# SAMR21_Xplained_Pro_Crystals.net
KiCad netlist of a schematic drawn in Altium Designer
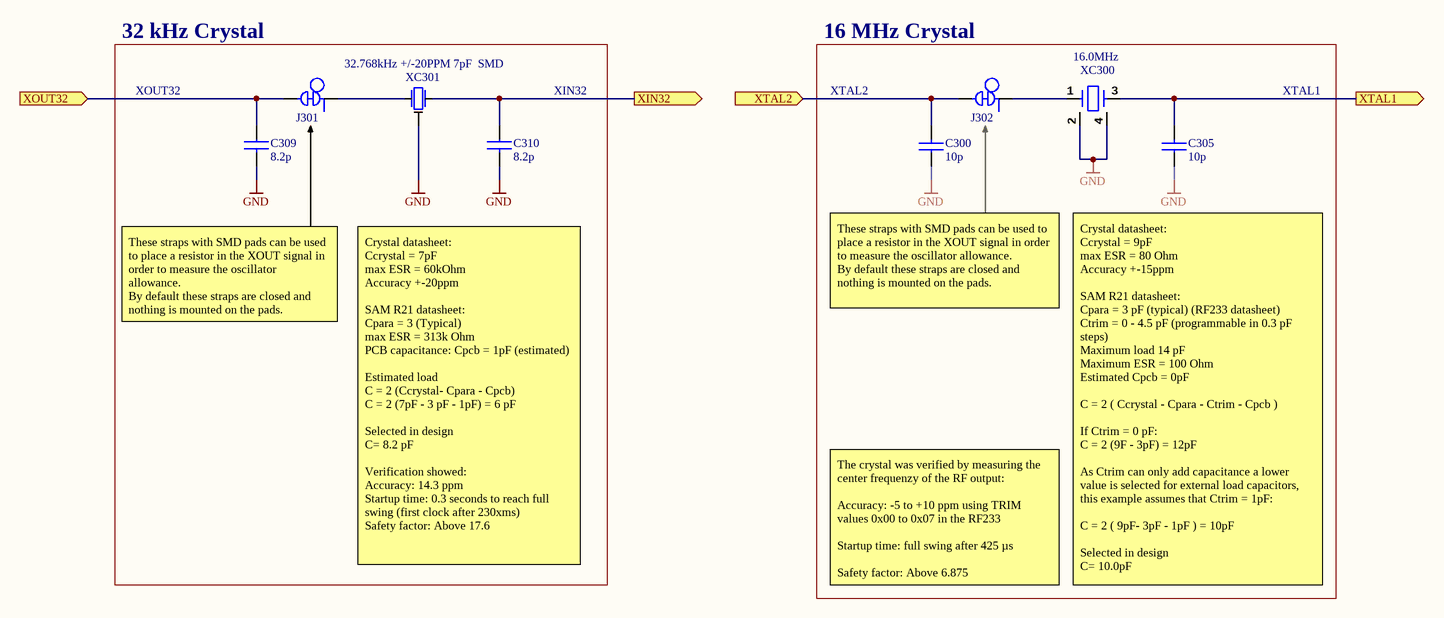
[diagram p0: SAMR21_Xplained_Pro_Crystals.SchDoc]

(export (version "E")
  (design (tool "Eeschema 10.0.6"))
  (components
    (comp (ref "C300")
      (value "10p")
      (footprint "AP1-00001")
      (description "Ceramic capacitor, SMD 0402, NP0, 50V, +/-5%")
      (fields (field (name "TOLERANCE") "50V, +/-5%") (field (name "Comment") "CAP-NONPOL"))
      (libsource (lib "AltiumDbLib") (part "CAP-NONPOL"))
    )
    (comp (ref "C305")
      (value "10p")
      (footprint "AP1-00001")
      (description "Ceramic capacitor, SMD 0402, NP0, 50V, +/-5%")
      (fields (field (name "TOLERANCE") "50V, +/-5%") (field (name "Comment") "CAP-NONPOL"))
      (libsource (lib "AltiumDbLib") (part "CAP-NONPOL"))
    )
    (comp (ref "C309")
      (value "8.2p")
      (footprint "AP1-00001")
      (description "Ceramic capacitor, SMD 0402, NP0, 50V, +/-5%")
      (fields (field (name "TOLERANCE") "50V, +/-5%") (field (name "Comment") "CAP-NONPOL"))
      (libsource (lib "AltiumDbLib") (part "CAP-NONPOL"))
    )
    (comp (ref "C310")
      (value "8.2p")
      (footprint "AP1-00001")
      (description "Ceramic capacitor, SMD 0402, NP0, 50V, +/-5%")
      (fields (field (name "TOLERANCE") "50V, +/-5%") (field (name "Comment") "CAP-NONPOL"))
      (libsource (lib "AltiumDbLib") (part "CAP-NONPOL"))
    )
    (comp (ref "J301")
      (value "SMD-STRAP_CLOSED")
      (footprint "AP8-00595")
      (description "Closed Link 0402")
      (libsource (lib "AltiumDbLib") (part "SMD-STRAP_CLOSED"))
    )
    (comp (ref "J302")
      (value "SMD-STRAP_CLOSED")
      (footprint "AP8-00595")
      (description "Closed Link 0402")
      (libsource (lib "AltiumDbLib") (part "SMD-STRAP_CLOSED"))
    )
    (comp (ref "XC300")
      (value "16.0MHz")
      (footprint "AP7-00061")
      (description "16MHz uXtal, 3.2 x 2.5 mm SMD, CL=9pF, 15PPM, ESR=80ohm(Max.")
      (fields (field (name "TOLERANCE") "15ppm") (field (name "MANUFACTURER") "Epson Toyocom"))
      (libsource (lib "AltiumDbLib") (part "TSX-3225"))
    )
    (comp (ref "XC301")
      (value "32.768kHz +/-20PPM 7pF  SMD")
      (footprint "AP7-00044")
      (description "32k768 crystal, +-20ppm, CL=7pF, max ESR 60kOhm, SMD")
      (fields (field (name "TOLERANCE") "+/- 20 PPM") (field (name "MANUFACTURER") "Micro Crystal"))
      (libsource (lib "AltiumDbLib") (part "CRYSTAL_2P_metal"))
    )
  )
  (nets
    (net (code "1") (name "/XIN32") (class "Default")
      (node (ref "C310") (pin "1") (pinfunction "1_1") (pintype "passive"))
      (node (ref "XC301") (pin "2") (pinfunction "2_2") (pintype "passive"))
    )
    (net (code "2") (name "/XOUT32") (class "Default")
      (node (ref "C309") (pin "1") (pinfunction "1_1") (pintype "passive"))
      (node (ref "J301") (pin "2") (pinfunction "2_2") (pintype "passive"))
    )
    (net (code "3") (name "/XTAL1") (class "Default")
      (node (ref "C305") (pin "2") (pinfunction "2_2") (pintype "passive"))
      (node (ref "XC300") (pin "3") (pinfunction "OUT_3") (pintype "passive"))
    )
    (net (code "4") (name "/XTAL2") (class "Default")
      (node (ref "C300") (pin "2") (pinfunction "2_2") (pintype "passive"))
      (node (ref "J302") (pin "2") (pinfunction "2_2") (pintype "passive"))
    )
    (net (code "5") (name "GND") (class "Default")
      (node (ref "C300") (pin "1") (pinfunction "1_1") (pintype "passive"))
      (node (ref "C305") (pin "1") (pinfunction "1_1") (pintype "passive"))
      (node (ref "C309") (pin "2") (pinfunction "2_2") (pintype "passive"))
      (node (ref "C310") (pin "2") (pinfunction "2_2") (pintype "passive"))
      (node (ref "XC300") (pin "2") (pinfunction "GND_2") (pintype "passive"))
      (node (ref "XC300") (pin "4") (pinfunction "GND_4") (pintype "passive"))
      (node (ref "XC301") (pin "3") (pinfunction "3_3") (pintype "passive"))
    )
    (net (code "6") (name "Net-(J301-Pad1)") (class "Default")
      (node (ref "J301") (pin "1") (pinfunction "1_1") (pintype "passive"))
      (node (ref "XC301") (pin "1") (pinfunction "1_1") (pintype "passive"))
    )
    (net (code "7") (name "Net-(XC300-IN)") (class "Default")
      (node (ref "J302") (pin "1") (pinfunction "1_1") (pintype "passive"))
      (node (ref "XC300") (pin "1") (pinfunction "IN_1") (pintype "passive"))
    )
  )
)
